# turbo-ds.net
KiCad netlist of a schematic drawn in EAGLE
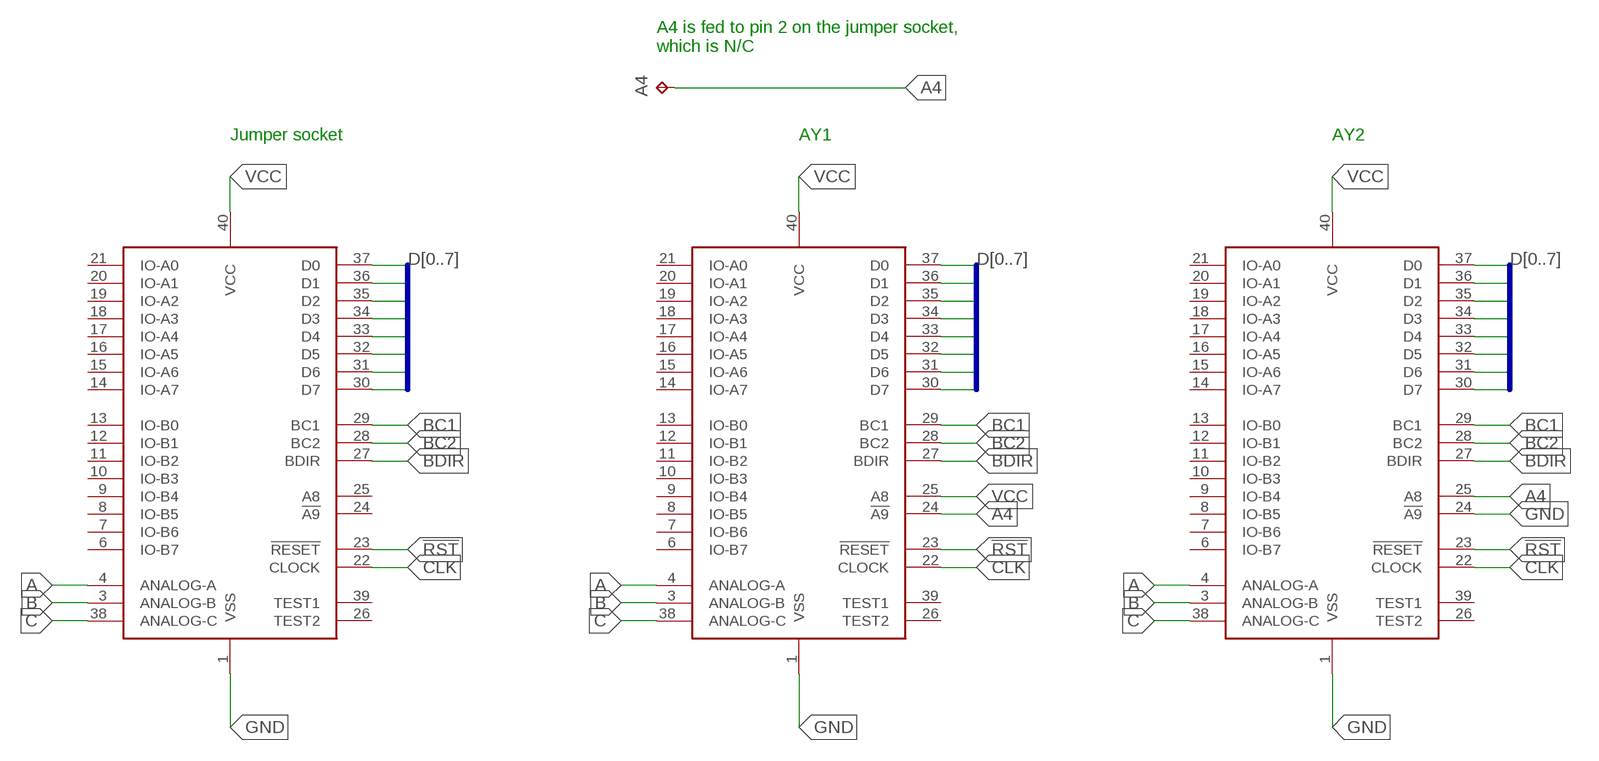
[diagram p0: schematic, sheet 1]

(export (version "E")
  (design (tool "Eeschema 10.0.6"))
  (components
    (comp (ref "A4")
      (value "TPB1,27")
      (footprint "eagle-import:B1,27")
      (libsource (lib "eagle-import") (part "TPB1,27"))
    )
    (comp (ref "AY1")
      (value "AY-3-8910")
      (footprint "eagle-import:DIL40")
      (libsource (lib "eagle-import") (part "AY-3-8910"))
    )
    (comp (ref "AY2")
      (value "AY-3-8910")
      (footprint "eagle-import:DIL40")
      (libsource (lib "eagle-import") (part "AY-3-8910"))
    )
    (comp (ref "INPUT")
      (value "AY-3-8910")
      (footprint "eagle-import:DIL40")
      (libsource (lib "eagle-import") (part "AY-3-8910"))
    )
  )
  (nets
    (net (code "1") (name "/D0") (class "Default")
      (node (ref "AY1") (pin "37") (pinfunction "D0_37") (pintype "input"))
      (node (ref "AY2") (pin "37") (pinfunction "D0_37") (pintype "input"))
      (node (ref "INPUT") (pin "37") (pinfunction "D0_37") (pintype "input"))
    )
    (net (code "2") (name "/D1") (class "Default")
      (node (ref "AY1") (pin "36") (pinfunction "D1_36") (pintype "input"))
      (node (ref "AY2") (pin "36") (pinfunction "D1_36") (pintype "input"))
      (node (ref "INPUT") (pin "36") (pinfunction "D1_36") (pintype "input"))
    )
    (net (code "3") (name "/D2") (class "Default")
      (node (ref "AY1") (pin "35") (pinfunction "D2_35") (pintype "input"))
      (node (ref "AY2") (pin "35") (pinfunction "D2_35") (pintype "input"))
      (node (ref "INPUT") (pin "35") (pinfunction "D2_35") (pintype "input"))
    )
    (net (code "4") (name "/D3") (class "Default")
      (node (ref "AY1") (pin "34") (pinfunction "D3_34") (pintype "input"))
      (node (ref "AY2") (pin "34") (pinfunction "D3_34") (pintype "input"))
      (node (ref "INPUT") (pin "34") (pinfunction "D3_34") (pintype "input"))
    )
    (net (code "5") (name "/D4") (class "Default")
      (node (ref "AY1") (pin "33") (pinfunction "D4_33") (pintype "input"))
      (node (ref "AY2") (pin "33") (pinfunction "D4_33") (pintype "input"))
      (node (ref "INPUT") (pin "33") (pinfunction "D4_33") (pintype "input"))
    )
    (net (code "6") (name "/D5") (class "Default")
      (node (ref "AY1") (pin "32") (pinfunction "D5_32") (pintype "input"))
      (node (ref "AY2") (pin "32") (pinfunction "D5_32") (pintype "input"))
      (node (ref "INPUT") (pin "32") (pinfunction "D5_32") (pintype "input"))
    )
    (net (code "7") (name "/D6") (class "Default")
      (node (ref "AY1") (pin "31") (pinfunction "D6_31") (pintype "input"))
      (node (ref "AY2") (pin "31") (pinfunction "D6_31") (pintype "input"))
      (node (ref "INPUT") (pin "31") (pinfunction "D6_31") (pintype "input"))
    )
    (net (code "8") (name "/D7") (class "Default")
      (node (ref "AY1") (pin "30") (pinfunction "D7_30") (pintype "input"))
      (node (ref "AY2") (pin "30") (pinfunction "D7_30") (pintype "input"))
      (node (ref "INPUT") (pin "30") (pinfunction "D7_30") (pintype "input"))
    )
    (net (code "9") (name "/~{RST}") (class "Default")
      (node (ref "AY1") (pin "23") (pinfunction "~{RESET}_23") (pintype "input"))
      (node (ref "AY2") (pin "23") (pinfunction "~{RESET}_23") (pintype "input"))
      (node (ref "INPUT") (pin "23") (pinfunction "~{RESET}_23") (pintype "input"))
    )
    (net (code "10") (name "A") (class "Default")
      (node (ref "AY1") (pin "4") (pinfunction "ANALOG-A_4") (pintype "output"))
      (node (ref "AY2") (pin "4") (pinfunction "ANALOG-A_4") (pintype "output"))
      (node (ref "INPUT") (pin "4") (pinfunction "ANALOG-A_4") (pintype "output"))
    )
    (net (code "11") (name "A4") (class "Default")
      (node (ref "A4") (pin "TP") (pinfunction "TP_TP") (pintype "input"))
      (node (ref "AY1") (pin "24") (pinfunction "~{A9}_24") (pintype "input"))
      (node (ref "AY2") (pin "25") (pinfunction "A8_25") (pintype "input"))
    )
    (net (code "12") (name "B") (class "Default")
      (node (ref "AY1") (pin "3") (pinfunction "ANALOG-B_3") (pintype "output"))
      (node (ref "AY2") (pin "3") (pinfunction "ANALOG-B_3") (pintype "output"))
      (node (ref "INPUT") (pin "3") (pinfunction "ANALOG-B_3") (pintype "output"))
    )
    (net (code "13") (name "BC1") (class "Default")
      (node (ref "AY1") (pin "29") (pinfunction "BC1_29") (pintype "input"))
      (node (ref "AY2") (pin "29") (pinfunction "BC1_29") (pintype "input"))
      (node (ref "INPUT") (pin "29") (pinfunction "BC1_29") (pintype "input"))
    )
    (net (code "14") (name "BC2") (class "Default")
      (node (ref "AY1") (pin "28") (pinfunction "BC2_28") (pintype "input"))
      (node (ref "AY2") (pin "28") (pinfunction "BC2_28") (pintype "input"))
      (node (ref "INPUT") (pin "28") (pinfunction "BC2_28") (pintype "input"))
    )
    (net (code "15") (name "BDIR") (class "Default")
      (node (ref "AY1") (pin "27") (pinfunction "BDIR_27") (pintype "input"))
      (node (ref "AY2") (pin "27") (pinfunction "BDIR_27") (pintype "input"))
      (node (ref "INPUT") (pin "27") (pinfunction "BDIR_27") (pintype "input"))
    )
    (net (code "16") (name "C") (class "Default")
      (node (ref "AY1") (pin "38") (pinfunction "ANALOG-C_38") (pintype "output"))
      (node (ref "AY2") (pin "38") (pinfunction "ANALOG-C_38") (pintype "output"))
      (node (ref "INPUT") (pin "38") (pinfunction "ANALOG-C_38") (pintype "output"))
    )
    (net (code "17") (name "CLK") (class "Default")
      (node (ref "AY1") (pin "22") (pinfunction "CLOCK_22") (pintype "input"))
      (node (ref "AY2") (pin "22") (pinfunction "CLOCK_22") (pintype "input"))
      (node (ref "INPUT") (pin "22") (pinfunction "CLOCK_22") (pintype "input"))
    )
    (net (code "18") (name "GND") (class "Default")
      (node (ref "AY1") (pin "1") (pinfunction "VSS_1") (pintype "power_in"))
      (node (ref "AY2") (pin "1") (pinfunction "VSS_1") (pintype "power_in"))
      (node (ref "AY2") (pin "24") (pinfunction "~{A9}_24") (pintype "input"))
      (node (ref "INPUT") (pin "1") (pinfunction "VSS_1") (pintype "power_in"))
    )
    (net (code "19") (name "VCC") (class "Default")
      (node (ref "AY1") (pin "25") (pinfunction "A8_25") (pintype "input"))
      (node (ref "AY1") (pin "40") (pinfunction "VCC_40") (pintype "power_in"))
      (node (ref "AY2") (pin "40") (pinfunction "VCC_40") (pintype "power_in"))
      (node (ref "INPUT") (pin "40") (pinfunction "VCC_40") (pintype "power_in"))
    )
    (net (code "20") (name "unconnected-(AY1-IO-A0-Pad21)") (class "Default")
      (node (ref "AY1") (pin "21") (pinfunction "IO-A0_21") (pintype "bidirectional"))
    )
    (net (code "21") (name "unconnected-(AY1-IO-A1-Pad20)") (class "Default")
      (node (ref "AY1") (pin "20") (pinfunction "IO-A1_20") (pintype "bidirectional"))
    )
    (net (code "22") (name "unconnected-(AY1-IO-A2-Pad19)") (class "Default")
      (node (ref "AY1") (pin "19") (pinfunction "IO-A2_19") (pintype "bidirectional"))
    )
    (net (code "23") (name "unconnected-(AY1-IO-A3-Pad18)") (class "Default")
      (node (ref "AY1") (pin "18") (pinfunction "IO-A3_18") (pintype "bidirectional"))
    )
    (net (code "24") (name "unconnected-(AY1-IO-A4-Pad17)") (class "Default")
      (node (ref "AY1") (pin "17") (pinfunction "IO-A4_17") (pintype "bidirectional"))
    )
    (net (code "25") (name "unconnected-(AY1-IO-A5-Pad16)") (class "Default")
      (node (ref "AY1") (pin "16") (pinfunction "IO-A5_16") (pintype "bidirectional"))
    )
    (net (code "26") (name "unconnected-(AY1-IO-A6-Pad15)") (class "Default")
      (node (ref "AY1") (pin "15") (pinfunction "IO-A6_15") (pintype "bidirectional"))
    )
    (net (code "27") (name "unconnected-(AY1-IO-A7-Pad14)") (class "Default")
      (node (ref "AY1") (pin "14") (pinfunction "IO-A7_14") (pintype "bidirectional"))
    )
    (net (code "28") (name "unconnected-(AY1-IO-B0-Pad13)") (class "Default")
      (node (ref "AY1") (pin "13") (pinfunction "IO-B0_13") (pintype "bidirectional"))
    )
    (net (code "29") (name "unconnected-(AY1-IO-B1-Pad12)") (class "Default")
      (node (ref "AY1") (pin "12") (pinfunction "IO-B1_12") (pintype "bidirectional"))
    )
    (net (code "30") (name "unconnected-(AY1-IO-B2-Pad11)") (class "Default")
      (node (ref "AY1") (pin "11") (pinfunction "IO-B2_11") (pintype "bidirectional"))
    )
    (net (code "31") (name "unconnected-(AY1-IO-B3-Pad10)") (class "Default")
      (node (ref "AY1") (pin "10") (pinfunction "IO-B3_10") (pintype "bidirectional"))
    )
    (net (code "32") (name "unconnected-(AY1-IO-B4-Pad9)") (class "Default")
      (node (ref "AY1") (pin "9") (pinfunction "IO-B4_9") (pintype "bidirectional"))
    )
    (net (code "33") (name "unconnected-(AY1-IO-B5-Pad8)") (class "Default")
      (node (ref "AY1") (pin "8") (pinfunction "IO-B5_8") (pintype "bidirectional"))
    )
    (net (code "34") (name "unconnected-(AY1-IO-B6-Pad7)") (class "Default")
      (node (ref "AY1") (pin "7") (pinfunction "IO-B6_7") (pintype "bidirectional"))
    )
    (net (code "35") (name "unconnected-(AY1-IO-B7-Pad6)") (class "Default")
      (node (ref "AY1") (pin "6") (pinfunction "IO-B7_6") (pintype "bidirectional"))
    )
    (net (code "36") (name "unconnected-(AY1-TEST1-Pad39)") (class "Default")
      (node (ref "AY1") (pin "39") (pinfunction "TEST1_39") (pintype "input"))
    )
    (net (code "37") (name "unconnected-(AY1-TEST2-Pad26)") (class "Default")
      (node (ref "AY1") (pin "26") (pinfunction "TEST2_26") (pintype "output"))
    )
    (net (code "38") (name "unconnected-(AY2-IO-A0-Pad21)") (class "Default")
      (node (ref "AY2") (pin "21") (pinfunction "IO-A0_21") (pintype "bidirectional"))
    )
    (net (code "39") (name "unconnected-(AY2-IO-A1-Pad20)") (class "Default")
      (node (ref "AY2") (pin "20") (pinfunction "IO-A1_20") (pintype "bidirectional"))
    )
    (net (code "40") (name "unconnected-(AY2-IO-A2-Pad19)") (class "Default")
      (node (ref "AY2") (pin "19") (pinfunction "IO-A2_19") (pintype "bidirectional"))
    )
    (net (code "41") (name "unconnected-(AY2-IO-A3-Pad18)") (class "Default")
      (node (ref "AY2") (pin "18") (pinfunction "IO-A3_18") (pintype "bidirectional"))
    )
    (net (code "42") (name "unconnected-(AY2-IO-A4-Pad17)") (class "Default")
      (node (ref "AY2") (pin "17") (pinfunction "IO-A4_17") (pintype "bidirectional"))
    )
    (net (code "43") (name "unconnected-(AY2-IO-A5-Pad16)") (class "Default")
      (node (ref "AY2") (pin "16") (pinfunction "IO-A5_16") (pintype "bidirectional"))
    )
    (net (code "44") (name "unconnected-(AY2-IO-A6-Pad15)") (class "Default")
      (node (ref "AY2") (pin "15") (pinfunction "IO-A6_15") (pintype "bidirectional"))
    )
    (net (code "45") (name "unconnected-(AY2-IO-A7-Pad14)") (class "Default")
      (node (ref "AY2") (pin "14") (pinfunction "IO-A7_14") (pintype "bidirectional"))
    )
    (net (code "46") (name "unconnected-(AY2-IO-B0-Pad13)") (class "Default")
      (node (ref "AY2") (pin "13") (pinfunction "IO-B0_13") (pintype "bidirectional"))
    )
    (net (code "47") (name "unconnected-(AY2-IO-B1-Pad12)") (class "Default")
      (node (ref "AY2") (pin "12") (pinfunction "IO-B1_12") (pintype "bidirectional"))
    )
    (net (code "48") (name "unconnected-(AY2-IO-B2-Pad11)") (class "Default")
      (node (ref "AY2") (pin "11") (pinfunction "IO-B2_11") (pintype "bidirectional"))
    )
    (net (code "49") (name "unconnected-(AY2-IO-B3-Pad10)") (class "Default")
      (node (ref "AY2") (pin "10") (pinfunction "IO-B3_10") (pintype "bidirectional"))
    )
    (net (code "50") (name "unconnected-(AY2-IO-B4-Pad9)") (class "Default")
      (node (ref "AY2") (pin "9") (pinfunction "IO-B4_9") (pintype "bidirectional"))
    )
    (net (code "51") (name "unconnected-(AY2-IO-B5-Pad8)") (class "Default")
      (node (ref "AY2") (pin "8") (pinfunction "IO-B5_8") (pintype "bidirectional"))
    )
    (net (code "52") (name "unconnected-(AY2-IO-B6-Pad7)") (class "Default")
      (node (ref "AY2") (pin "7") (pinfunction "IO-B6_7") (pintype "bidirectional"))
    )
    (net (code "53") (name "unconnected-(AY2-IO-B7-Pad6)") (class "Default")
      (node (ref "AY2") (pin "6") (pinfunction "IO-B7_6") (pintype "bidirectional"))
    )
    (net (code "54") (name "unconnected-(AY2-TEST1-Pad39)") (class "Default")
      (node (ref "AY2") (pin "39") (pinfunction "TEST1_39") (pintype "input"))
    )
    (net (code "55") (name "unconnected-(AY2-TEST2-Pad26)") (class "Default")
      (node (ref "AY2") (pin "26") (pinfunction "TEST2_26") (pintype "output"))
    )
    (net (code "56") (name "unconnected-(INPUT-A8-Pad25)") (class "Default")
      (node (ref "INPUT") (pin "25") (pinfunction "A8_25") (pintype "input"))
    )
    (net (code "57") (name "unconnected-(INPUT-IO-A0-Pad21)") (class "Default")
      (node (ref "INPUT") (pin "21") (pinfunction "IO-A0_21") (pintype "bidirectional"))
    )
    (net (code "58") (name "unconnected-(INPUT-IO-A1-Pad20)") (class "Default")
      (node (ref "INPUT") (pin "20") (pinfunction "IO-A1_20") (pintype "bidirectional"))
    )
    (net (code "59") (name "unconnected-(INPUT-IO-A2-Pad19)") (class "Default")
      (node (ref "INPUT") (pin "19") (pinfunction "IO-A2_19") (pintype "bidirectional"))
    )
    (net (code "60") (name "unconnected-(INPUT-IO-A3-Pad18)") (class "Default")
      (node (ref "INPUT") (pin "18") (pinfunction "IO-A3_18") (pintype "bidirectional"))
    )
    (net (code "61") (name "unconnected-(INPUT-IO-A4-Pad17)") (class "Default")
      (node (ref "INPUT") (pin "17") (pinfunction "IO-A4_17") (pintype "bidirectional"))
    )
    (net (code "62") (name "unconnected-(INPUT-IO-A5-Pad16)") (class "Default")
      (node (ref "INPUT") (pin "16") (pinfunction "IO-A5_16") (pintype "bidirectional"))
    )
    (net (code "63") (name "unconnected-(INPUT-IO-A6-Pad15)") (class "Default")
      (node (ref "INPUT") (pin "15") (pinfunction "IO-A6_15") (pintype "bidirectional"))
    )
    (net (code "64") (name "unconnected-(INPUT-IO-A7-Pad14)") (class "Default")
      (node (ref "INPUT") (pin "14") (pinfunction "IO-A7_14") (pintype "bidirectional"))
    )
    (net (code "65") (name "unconnected-(INPUT-IO-B0-Pad13)") (class "Default")
      (node (ref "INPUT") (pin "13") (pinfunction "IO-B0_13") (pintype "bidirectional"))
    )
    (net (code "66") (name "unconnected-(INPUT-IO-B1-Pad12)") (class "Default")
      (node (ref "INPUT") (pin "12") (pinfunction "IO-B1_12") (pintype "bidirectional"))
    )
    (net (code "67") (name "unconnected-(INPUT-IO-B2-Pad11)") (class "Default")
      (node (ref "INPUT") (pin "11") (pinfunction "IO-B2_11") (pintype "bidirectional"))
    )
    (net (code "68") (name "unconnected-(INPUT-IO-B3-Pad10)") (class "Default")
      (node (ref "INPUT") (pin "10") (pinfunction "IO-B3_10") (pintype "bidirectional"))
    )
    (net (code "69") (name "unconnected-(INPUT-IO-B4-Pad9)") (class "Default")
      (node (ref "INPUT") (pin "9") (pinfunction "IO-B4_9") (pintype "bidirectional"))
    )
    (net (code "70") (name "unconnected-(INPUT-IO-B5-Pad8)") (class "Default")
      (node (ref "INPUT") (pin "8") (pinfunction "IO-B5_8") (pintype "bidirectional"))
    )
    (net (code "71") (name "unconnected-(INPUT-IO-B6-Pad7)") (class "Default")
      (node (ref "INPUT") (pin "7") (pinfunction "IO-B6_7") (pintype "bidirectional"))
    )
    (net (code "72") (name "unconnected-(INPUT-IO-B7-Pad6)") (class "Default")
      (node (ref "INPUT") (pin "6") (pinfunction "IO-B7_6") (pintype "bidirectional"))
    )
    (net (code "73") (name "unconnected-(INPUT-TEST1-Pad39)") (class "Default")
      (node (ref "INPUT") (pin "39") (pinfunction "TEST1_39") (pintype "input"))
    )
    (net (code "74") (name "unconnected-(INPUT-TEST2-Pad26)") (class "Default")
      (node (ref "INPUT") (pin "26") (pinfunction "TEST2_26") (pintype "output"))
    )
    (net (code "75") (name "unconnected-(INPUT-~{A9}-Pad24)") (class "Default")
      (node (ref "INPUT") (pin "24") (pinfunction "~{A9}_24") (pintype "input"))
    )
  )
)
